# Spy_Circuits_3-transistor_Page-20.net
KiCad netlist of a schematic drawn in EAGLE
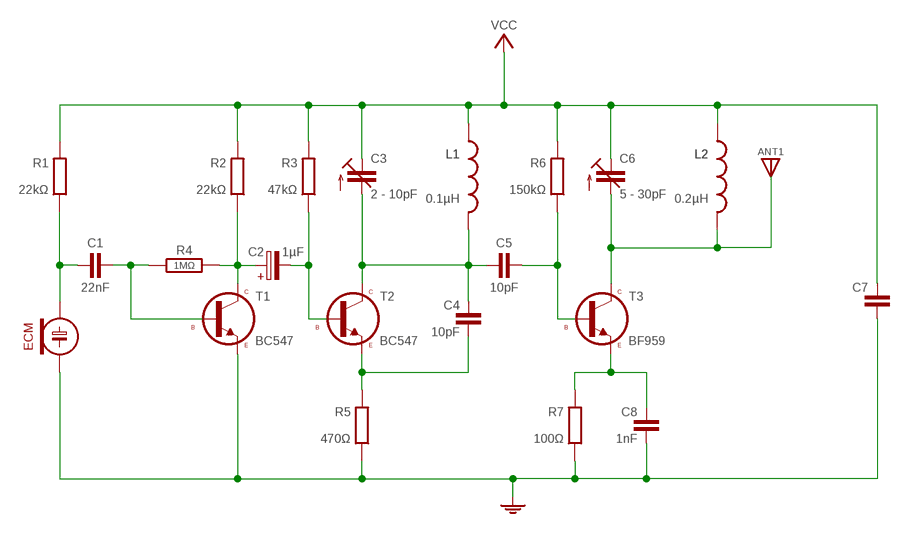
[diagram p0: schematic, sheet 1]

(export (version "E")
  (design (tool "Eeschema 10.0.6"))
  (components
    (comp (ref "ANT1")
      (value "ANT")
      (footprint "eagle-import:SPAD")
      (libsource (lib "eagle-import") (part "ANT"))
    )
    (comp (ref "C1")
      (value "22nF")
      (footprint "eagle-import:C025-015X024")
      (libsource (lib "eagle-import") (part "C-H025-015X024"))
    )
    (comp (ref "C2")
      (value "1µF")
      (footprint "eagle-import:E2,5-3")
      (libsource (lib "eagle-import") (part "CPOL-HE2,5-3"))
    )
    (comp (ref "C3")
      (value "2 - 10pF")
      (footprint "eagle-import:TRIM-2222-808-45")
      (libsource (lib "eagle-import") (part "C-TR-PH201272222-808-45-2PIN"))
    )
    (comp (ref "C4")
      (value "10pF")
      (footprint "eagle-import:C025-015X024_V")
      (libsource (lib "eagle-import") (part "C025-015X024/V"))
    )
    (comp (ref "C5")
      (value "10pF")
      (footprint "eagle-import:C025-015X024")
      (libsource (lib "eagle-import") (part "C-H025-015X024"))
    )
    (comp (ref "C6")
      (value "5 - 30pF")
      (footprint "eagle-import:TRIM-C-BIG")
      (libsource (lib "eagle-import") (part "C-TR-PH20127-C-BIG"))
    )
    (comp (ref "C7")
      (value "C025-015X024/V")
      (footprint "eagle-import:C025-015X024_V")
      (libsource (lib "eagle-import") (part "C025-015X024/V"))
    )
    (comp (ref "C8")
      (value "1nF")
      (footprint "eagle-import:C025-015X024_V")
      (libsource (lib "eagle-import") (part "C025-015X024/V"))
    )
    (comp (ref "ECM1")
      (value "ECM-4")
      (footprint "eagle-import:ECM-4")
      (libsource (lib "eagle-import") (part "ECM-4"))
    )
    (comp (ref "L1")
      (value "0.1µH")
      (footprint "eagle-import:L-04_8V-2-M")
      (libsource (lib "eagle-import") (part "L04/8V-2-M"))
    )
    (comp (ref "L2")
      (value "0.2µH")
      (footprint "eagle-import:L-08-10_5")
      (libsource (lib "eagle-import") (part "L08-10/5"))
    )
    (comp (ref "R1")
      (value "22kΩ")
      (footprint "eagle-import:0204_2")
      (libsource (lib "eagle-import") (part "R0204/2"))
    )
    (comp (ref "R2")
      (value "22kΩ")
      (footprint "eagle-import:0204_10-V")
      (libsource (lib "eagle-import") (part "R0204/10-V"))
    )
    (comp (ref "R3")
      (value "47kΩ")
      (footprint "eagle-import:0204_10")
      (libsource (lib "eagle-import") (part "R0204/10"))
    )
    (comp (ref "R4")
      (value "1MΩ")
      (footprint "eagle-import:0202_2V")
      (libsource (lib "eagle-import") (part "R-H0202/2V"))
    )
    (comp (ref "R5")
      (value "470Ω")
      (footprint "eagle-import:0204_2")
      (libsource (lib "eagle-import") (part "R0204/2"))
    )
    (comp (ref "R6")
      (value "150kΩ")
      (footprint "eagle-import:0204_2")
      (libsource (lib "eagle-import") (part "R0204/2"))
    )
    (comp (ref "R7")
      (value "100Ω")
      (footprint "eagle-import:0204_2")
      (libsource (lib "eagle-import") (part "R0204/2"))
    )
    (comp (ref "S1")
      (value "VCC_GNDL")
      (footprint "eagle-import:SPAD-+")
      (libsource (lib "eagle-import") (part "VCC_GNDL"))
    )
    (comp (ref "T1")
      (value "BC547")
      (footprint "eagle-import:TO92")
      (libsource (lib "eagle-import") (part "BC547"))
    )
    (comp (ref "T2")
      (value "BC547")
      (footprint "eagle-import:TO92")
      (libsource (lib "eagle-import") (part "BC547"))
    )
    (comp (ref "T3")
      (value "BF959")
      (footprint "eagle-import:TO92-CEB")
      (libsource (lib "eagle-import") (part "BF959"))
    )
  )
  (nets
    (net (code "1") (name "Net-(C3-A)") (class "Default")
      (node (ref "C3") (pin "2") (pinfunction "A_2") (pintype "passive"))
      (node (ref "C4") (pin "1") (pinfunction "1_1") (pintype "passive"))
      (node (ref "C5") (pin "1") (pinfunction "1_1") (pintype "passive"))
      (node (ref "L1") (pin "1") (pinfunction "2_1") (pintype "passive"))
      (node (ref "T2") (pin "1") (pinfunction "C_1") (pintype "passive"))
    )
    (net (code "2") (name "Net-(C3-E)") (class "Default")
      (node (ref "C3") (pin "1") (pinfunction "E_1") (pintype "passive"))
      (node (ref "C6") (pin "P$3") (pinfunction "E_P$3") (pintype "passive"))
      (node (ref "C7") (pin "1") (pinfunction "1_1") (pintype "passive"))
      (node (ref "L1") (pin "2") (pinfunction "1_2") (pintype "passive"))
      (node (ref "L2") (pin "1") (pinfunction "1_1") (pintype "passive"))
      (node (ref "R1") (pin "1") (pinfunction "2_1") (pintype "passive"))
      (node (ref "R2") (pin "1") (pinfunction "2_1") (pintype "passive"))
      (node (ref "R3") (pin "1") (pinfunction "2_1") (pintype "passive"))
      (node (ref "R6") (pin "1") (pinfunction "2_1") (pintype "passive"))
      (node (ref "S1") (pin "2") (pinfunction "VCC_2") (pintype "power_in"))
    )
    (net (code "3") (name "Net-(C6-A)") (class "Default")
      (node (ref "ANT1") (pin "1") (pinfunction "1_1") (pintype "output"))
      (node (ref "C6") (pin "P$1") (pinfunction "A_P$1") (pintype "passive"))
      (node (ref "L2") (pin "2") (pinfunction "2_2") (pintype "passive"))
      (node (ref "T3") (pin "C") (pinfunction "C_C") (pintype "passive"))
    )
    (net (code "4") (name "Net-(ECM1-+)") (class "Default")
      (node (ref "C1") (pin "1") (pinfunction "1_1") (pintype "passive"))
      (node (ref "ECM1") (pin "1") (pinfunction "+_1") (pintype "passive"))
      (node (ref "R1") (pin "2") (pinfunction "1_2") (pintype "passive"))
    )
    (net (code "5") (name "Net-(ECM1--)") (class "Default")
      (node (ref "C7") (pin "2") (pinfunction "2_2") (pintype "passive"))
      (node (ref "C8") (pin "2") (pinfunction "2_2") (pintype "passive"))
      (node (ref "ECM1") (pin "2") (pinfunction "-_2") (pintype "passive"))
      (node (ref "R5") (pin "2") (pinfunction "1_2") (pintype "passive"))
      (node (ref "R7") (pin "2") (pinfunction "1_2") (pintype "passive"))
      (node (ref "S1") (pin "1") (pinfunction "GND_1") (pintype "power_in"))
      (node (ref "T1") (pin "3") (pinfunction "E_3") (pintype "passive"))
    )
    (net (code "6") (name "Net-(R2-1)") (class "Default")
      (node (ref "C2") (pin "+") (pinfunction "+_+") (pintype "passive"))
      (node (ref "R2") (pin "2") (pinfunction "1_2") (pintype "passive"))
      (node (ref "R4") (pin "2") (pinfunction "2_2") (pintype "passive"))
      (node (ref "T1") (pin "1") (pinfunction "C_1") (pintype "passive"))
    )
    (net (code "7") (name "Net-(R3-1)") (class "Default")
      (node (ref "C2") (pin "-") (pinfunction "-_-") (pintype "passive"))
      (node (ref "R3") (pin "2") (pinfunction "1_2") (pintype "passive"))
      (node (ref "T2") (pin "2") (pinfunction "B_2") (pintype "passive"))
    )
    (net (code "8") (name "Net-(R5-2)") (class "Default")
      (node (ref "C4") (pin "2") (pinfunction "2_2") (pintype "passive"))
      (node (ref "R5") (pin "1") (pinfunction "2_1") (pintype "passive"))
      (node (ref "T2") (pin "3") (pinfunction "E_3") (pintype "passive"))
    )
    (net (code "9") (name "Net-(R6-1)") (class "Default")
      (node (ref "C5") (pin "2") (pinfunction "2_2") (pintype "passive"))
      (node (ref "R6") (pin "2") (pinfunction "1_2") (pintype "passive"))
      (node (ref "T3") (pin "B") (pinfunction "B_B") (pintype "passive"))
    )
    (net (code "10") (name "Net-(R7-2)") (class "Default")
      (node (ref "C8") (pin "1") (pinfunction "1_1") (pintype "passive"))
      (node (ref "R7") (pin "1") (pinfunction "2_1") (pintype "passive"))
      (node (ref "T3") (pin "E") (pinfunction "E_E") (pintype "passive"))
    )
    (net (code "11") (name "Net-(T1-B)") (class "Default")
      (node (ref "C1") (pin "2") (pinfunction "2_2") (pintype "passive"))
      (node (ref "R4") (pin "1") (pinfunction "1_1") (pintype "passive"))
      (node (ref "T1") (pin "2") (pinfunction "B_2") (pintype "passive"))
    )
  )
)
